# ReboostV2_CAN.net
KiCad netlist of a schematic drawn in Altium Designer
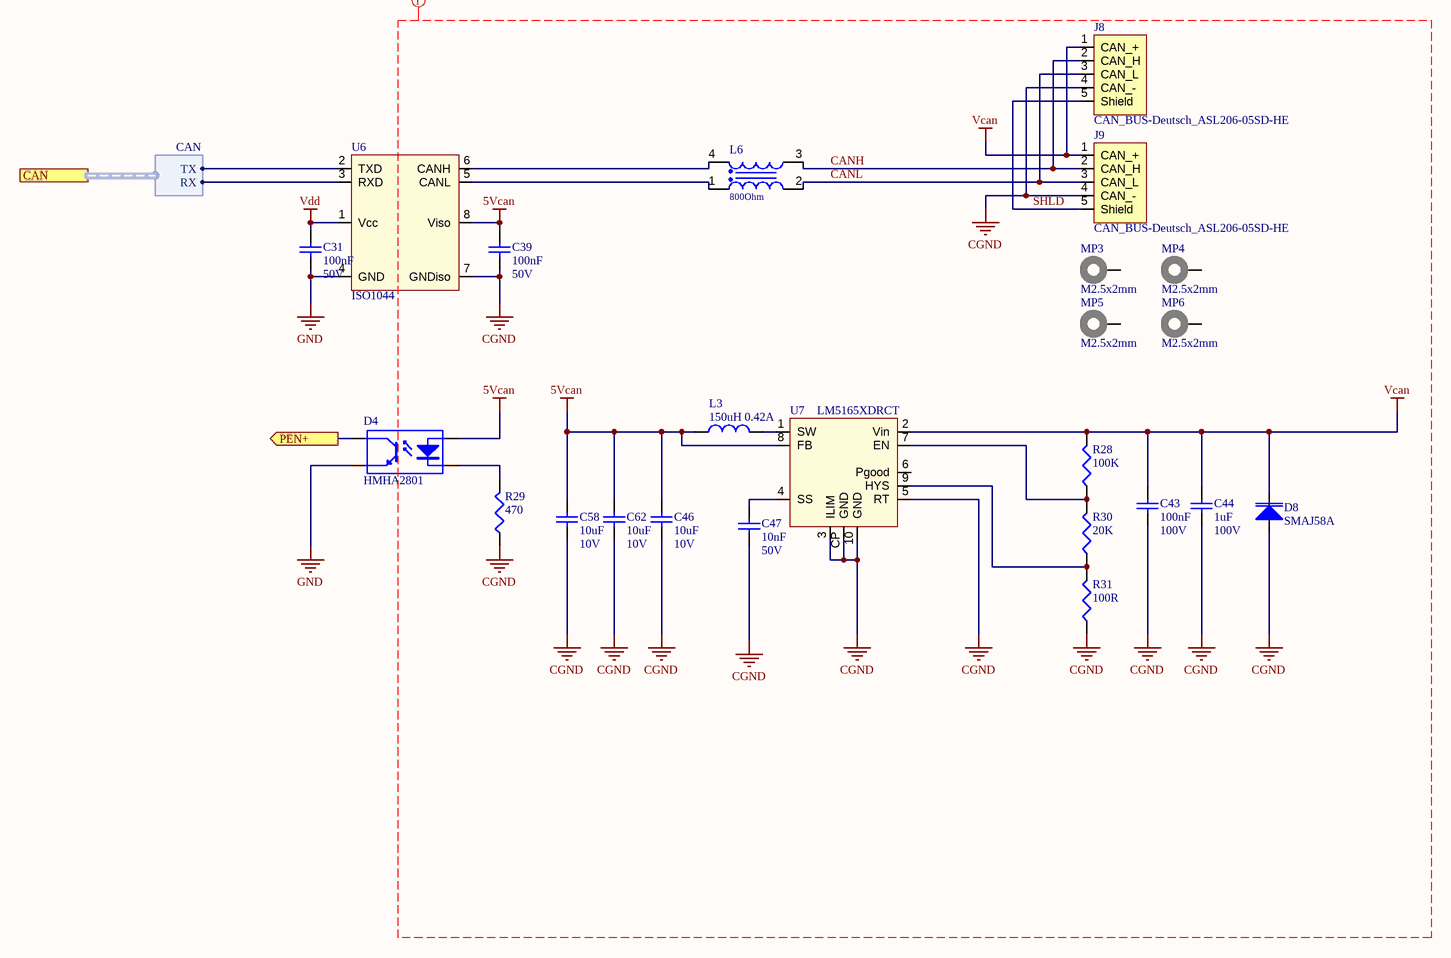
[diagram p0: ReboostV2_CAN.SchDoc]

(export (version "E")
  (design (tool "Eeschema 10.0.6"))
  (components
    (comp (ref "C31")
      (value "100nF")
      (footprint "C0603")
      (description "Capacitor, 100nF, 50V, X7R")
      (fields
        (field (name "VOLTAGE RATING") "50V")
        (field (name "MANUFACTURER") "MULTICOMP")
        (field (name "MANUFACTURER PART NUMBER") "MCCA000255")
      )
      (libsource (lib "Reboostv2") (part "100nF/0603/CER/50V"))
    )
    (comp (ref "C39")
      (value "100nF")
      (footprint "C0603")
      (description "Capacitor, 100nF, 50V, X7R")
      (fields
        (field (name "VOLTAGE RATING") "50V")
        (field (name "MANUFACTURER") "MULTICOMP")
        (field (name "MANUFACTURER PART NUMBER") "MCCA000255")
      )
      (libsource (lib "Reboostv2") (part "100nF/0603/CER/50V"))
    )
    (comp (ref "C43")
      (value "100nF")
      (footprint "C-0805")
      (description "Capacitor, 100nF, 100V, X7R")
      (fields
        (field (name "VOLTAGE RATING") "100V")
        (field (name "MANUFACTURER") "KEMET")
        (field (name "MANUFACTURER PART NUMBER") "C0805C104K1RACTU")
      )
      (libsource (lib "Reboostv2") (part "100nF/0805/CER/100V"))
    )
    (comp (ref "C44")
      (value "1uF")
      (footprint "C-1206")
      (description "Capacitor, 1uF, 100V, X7R")
      (fields
        (field (name "VOLTAGE RATING") "100V")
        (field (name "MANUFACTURER") "AVX")
        (field (name "MANUFACTURER PART NUMBER") "12061C105K4Z2A")
      )
      (libsource (lib "Reboostv2") (part "1uF/1206/CER/100V"))
    )
    (comp (ref "C46")
      (value "10uF")
      (footprint "C-0805")
      (description "Capacitor, 10uF, 10V, X7R")
      (fields
        (field (name "VOLTAGE RATING") "10V")
        (field (name "MANUFACTURER") "MURATA")
        (field (name "MANUFACTURER PART NUMBER") "GRM21BR71A106KE51L")
      )
      (libsource (lib "Reboostv2") (part "10uF/0805/CER/10V"))
    )
    (comp (ref "C47")
      (value "10nF")
      (footprint "C0603")
      (description "Capacitor, 10nF, 50V, X7R")
      (fields
        (field (name "VOLTAGE RATING") "50V")
        (field (name "MANUFACTURER") "KEMET")
        (field (name "MANUFACTURER PART NUMBER") "C0603C103K5RACTU")
      )
      (libsource (lib "Reboostv2") (part "10nF/0603/CER/50V"))
    )
    (comp (ref "C58")
      (value "10uF")
      (footprint "C-0805")
      (description "Capacitor, 10uF, 10V, X7R")
      (fields
        (field (name "VOLTAGE RATING") "10V")
        (field (name "MANUFACTURER") "MURATA")
        (field (name "MANUFACTURER PART NUMBER") "GRM21BR71A106KE51L")
      )
      (libsource (lib "Reboostv2") (part "10uF/0805/CER/10V"))
    )
    (comp (ref "C62")
      (value "10uF")
      (footprint "C-0805")
      (description "Capacitor, 10uF, 10V, X7R")
      (fields
        (field (name "VOLTAGE RATING") "10V")
        (field (name "MANUFACTURER") "MURATA")
        (field (name "MANUFACTURER PART NUMBER") "GRM21BR71A106KE51L")
      )
      (libsource (lib "Reboostv2") (part "10uF/0805/CER/10V"))
    )
    (comp (ref "D4")
      (value "HMHA2801")
      (footprint "FSOP4")
      (description "Optocoupler, Vout:80V, Iin:0.01A")
      (fields (field (name "MANUFACTURER") "FAIRCHILD SEMICONDUCTOR"))
      (libsource (lib "Reboostv2") (part "HMHA2801"))
    )
    (comp (ref "D8")
      (value "SMAJ58A")
      (footprint "SMA")
      (description "Diode TVS, Vrwm: 58V, Vbr: 71.2V, Vc: 93.6V, Ippm: 4.3A")
      (fields (field (name "MANUFACTURER") "MULTICOMP"))
      (libsource (lib "Reboostv2") (part "SMAJ58A"))
    )
    (comp (ref "J8")
      (value "CAN_BUS-Deutsch_ASL206-05SD-HE")
      (footprint "ASL206-05SD-HE")
      (fields
        (field (name "MANUFACTURER") "TE Connectivity")
        (field (name "MANUFACTURER PART NUMBER") "ASL206-05SD-HE")
      )
      (libsource (lib "Reboostv2") (part "CMP-024-0003-1"))
    )
    (comp (ref "J9")
      (value "CAN_BUS-Deutsch_ASL206-05SD-HE")
      (footprint "ASL206-05SD-HE")
      (fields
        (field (name "MANUFACTURER") "TE Connectivity")
        (field (name "MANUFACTURER PART NUMBER") "ASL206-05SD-HE")
      )
      (libsource (lib "Reboostv2") (part "CMP-024-0003-1"))
    )
    (comp (ref "L3")
      (value "150uH 0.42A")
      (footprint "WE-TPC 4828, MH")
      (description "150UH, 30%, 0.42A")
      (fields
        (field (name "MANUFACTURER") "Wurth Elektronik")
        (field (name "MANUFACTURER PART NUMBER") "744043151")
      )
      (libsource (lib "Reboostv2") (part "744043151"))
    )
    (comp (ref "L6")
      (value "800Ohm")
      (footprint "WE-CNSW_1812")
      (description "WE-CNSW SMT Common Mode Line Filter, size 1812, 800Ohm, 1A, 60V")
      (fields
        (field (name "MANUFACTURER PART NUMBER") "744235801")
        (field (name "MANUFACTURER") "Wurth Elektronik")
      )
      (libsource (lib "Reboostv2") (part "744235801"))
    )
    (comp (ref "MP3")
      (value "M2.5x2mm")
      (footprint "9774020151")
      (description "WA-SMSI SMT Steel Spacer, M2.5 Thread Internal, OD 5.1mm, M2.5x2mm")
      (fields
        (field (name "MANUFACTURER PART NUMBER") "9774020151")
        (field (name "MANUFACTURER") "Wurth Elektronik")
      )
      (libsource (lib "Reboostv2") (part "9774020151"))
    )
    (comp (ref "MP4")
      (value "M2.5x2mm")
      (footprint "9774020151")
      (description "WA-SMSI SMT Steel Spacer, M2.5 Thread Internal, OD 5.1mm, M2.5x2mm")
      (fields
        (field (name "MANUFACTURER PART NUMBER") "9774020151")
        (field (name "MANUFACTURER") "Wurth Elektronik")
      )
      (libsource (lib "Reboostv2") (part "9774020151"))
    )
    (comp (ref "MP5")
      (value "M2.5x2mm")
      (footprint "9774020151")
      (description "WA-SMSI SMT Steel Spacer, M2.5 Thread Internal, OD 5.1mm, M2.5x2mm")
      (fields
        (field (name "MANUFACTURER PART NUMBER") "9774020151")
        (field (name "MANUFACTURER") "Wurth Elektronik")
      )
      (libsource (lib "Reboostv2") (part "9774020151"))
    )
    (comp (ref "MP6")
      (value "M2.5x2mm")
      (footprint "9774020151")
      (description "WA-SMSI SMT Steel Spacer, M2.5 Thread Internal, OD 5.1mm, M2.5x2mm")
      (fields
        (field (name "MANUFACTURER PART NUMBER") "9774020151")
        (field (name "MANUFACTURER") "Wurth Elektronik")
      )
      (libsource (lib "Reboostv2") (part "9774020151"))
    )
    (comp (ref "R28")
      (value "100K")
      (footprint "0603")
      (description "Resistor, 100K, 1%, 0.063W, 50V, 100PPM, 0603")
      (fields
        (field (name "MANUFACTURER") "VISHAY DRALORIC")
        (field (name "MANUFACTURER PART NUMBER") "CRCW0603100KFKEA")
      )
      (libsource (lib "Reboostv2") (part "100K/0603/0063W/50V"))
    )
    (comp (ref "R29")
      (value "470")
      (footprint "0603")
      (description "Resistor, 470, 1%, 0.063W, 50V, 100PPM, 0603")
      (fields
        (field (name "MANUFACTURER") "VISHAY DRALORIC")
        (field (name "MANUFACTURER PART NUMBER") "CRCW0603470RFKEA")
      )
      (libsource (lib "Reboostv2") (part "470/0603/0063W/50V"))
    )
    (comp (ref "R30")
      (value "20K")
      (footprint "0603")
      (description "Resistor, 20K, 1%, 0.063W, 50V, 100PPM, 0603")
      (fields
        (field (name "MANUFACTURER") "VISHAY DRALORIC")
        (field (name "MANUFACTURER PART NUMBER") "CRCW060320K0FKEA")
      )
      (libsource (lib "Reboostv2") (part "20K/0603/0063W/50V"))
    )
    (comp (ref "R31")
      (value "100R")
      (footprint "0603")
      (description "Resistor, 100R, 1%, 0.063W, 50V, 200PPM, 0603")
      (fields
        (field (name "MANUFACTURER") "VISHAY DRALORIC")
        (field (name "MANUFACTURER PART NUMBER") "CRCW0603100RFKEA")
      )
      (libsource (lib "Reboostv2") (part "100/0603/0063W/50V"))
    )
    (comp (ref "U6")
      (value "ISO1044")
      (footprint "SO-8")
      (description "ISO1044 Isolated CAN FD Transceiver in Small Package")
      (fields
        (field (name "MANUFACTURER") "Texas Instruments")
        (field (name "MANUFACTURER PART NUMBER") "ISO1044BD")
      )
      (libsource (lib "Reboostv2") (part "ISO1044"))
    )
    (comp (ref "U7")
      (value "LM5165XDRCT")
      (footprint "PWSON10")
      (description "Buck Vreg 150mA 5Vout 5-65Vin")
      (fields (field (name "MANUFACTURER") "Texas Instruments"))
      (libsource (lib "Reboostv2") (part "LM5165X"))
    )
  )
  (nets
    (net (code "2") (name "/CANH") (class "Default")
      (node (ref "J8") (pin "2") (pinfunction "CAN_H_2") (pintype "passive"))
      (node (ref "J9") (pin "2") (pinfunction "CAN_H_2") (pintype "passive"))
      (node (ref "L6") (pin "3") (pinfunction "3_3") (pintype "passive"))
    )
    (net (code "3") (name "/CANL") (class "Default")
      (node (ref "J8") (pin "3") (pinfunction "CAN_L_3") (pintype "passive"))
      (node (ref "J9") (pin "3") (pinfunction "CAN_L_3") (pintype "passive"))
      (node (ref "L6") (pin "2") (pinfunction "2_2") (pintype "passive"))
    )
    (net (code "4") (name "/PEN+") (class "Default")
      (node (ref "D4") (pin "4") (pinfunction "C1_4") (pintype "passive"))
    )
    (net (code "5") (name "/RX") (class "Default")
      (node (ref "U6") (pin "3") (pinfunction "RXD_3") (pintype "passive"))
    )
    (net (code "6") (name "/SHLD") (class "Default")
      (node (ref "J8") (pin "5") (pinfunction "Shield_5") (pintype "passive"))
      (node (ref "J9") (pin "5") (pinfunction "Shield_5") (pintype "passive"))
    )
    (net (code "7") (name "/TX") (class "Default")
      (node (ref "U6") (pin "2") (pinfunction "TXD_2") (pintype "passive"))
    )
    (net (code "9") (name "5Vcan") (class "Default")
      (node (ref "C39") (pin "2") (pinfunction "2_2") (pintype "passive"))
      (node (ref "C46") (pin "2") (pinfunction "2_2") (pintype "passive"))
      (node (ref "C58") (pin "2") (pinfunction "2_2") (pintype "passive"))
      (node (ref "C62") (pin "2") (pinfunction "2_2") (pintype "passive"))
      (node (ref "D4") (pin "1") (pinfunction "A1_1") (pintype "passive"))
      (node (ref "L3") (pin "2") (pinfunction "2_2") (pintype "passive"))
      (node (ref "U6") (pin "8") (pinfunction "Viso_8") (pintype "passive"))
      (node (ref "U7") (pin "8") (pinfunction "FB_8") (pintype "passive"))
    )
    (net (code "10") (name "CGND") (class "Default")
      (node (ref "C39") (pin "1") (pinfunction "1_1") (pintype "passive"))
      (node (ref "C43") (pin "1") (pinfunction "1_1") (pintype "passive"))
      (node (ref "C44") (pin "1") (pinfunction "1_1") (pintype "passive"))
      (node (ref "C46") (pin "1") (pinfunction "1_1") (pintype "passive"))
      (node (ref "C47") (pin "1") (pinfunction "1_1") (pintype "passive"))
      (node (ref "C58") (pin "1") (pinfunction "1_1") (pintype "passive"))
      (node (ref "C62") (pin "1") (pinfunction "1_1") (pintype "passive"))
      (node (ref "D8") (pin "1") (pinfunction "1_1") (pintype "passive"))
      (node (ref "J8") (pin "4") (pinfunction "CAN_-_4") (pintype "passive"))
      (node (ref "J9") (pin "4") (pinfunction "CAN_-_4") (pintype "passive"))
      (node (ref "R29") (pin "1") (pinfunction "1_1") (pintype "passive"))
      (node (ref "R31") (pin "1") (pinfunction "1_1") (pintype "passive"))
      (node (ref "U6") (pin "7") (pinfunction "GNDiso_7") (pintype "passive"))
      (node (ref "U7") (pin "10") (pinfunction "GND_10") (pintype "passive"))
      (node (ref "U7") (pin "3") (pinfunction "ILIM_3") (pintype "passive"))
      (node (ref "U7") (pin "5") (pinfunction "RT_5") (pintype "passive"))
      (node (ref "U7") (pin "CP") (pinfunction "GND_CP") (pintype "passive"))
    )
    (net (code "11") (name "GND") (class "Default")
      (node (ref "C31") (pin "1") (pinfunction "1_1") (pintype "passive"))
      (node (ref "D4") (pin "3") (pinfunction "E1_3") (pintype "passive"))
      (node (ref "U6") (pin "4") (pinfunction "GND_4") (pintype "passive"))
    )
    (net (code "12") (name "Net-(D4-K1)") (class "Default")
      (node (ref "D4") (pin "2") (pinfunction "K1_2") (pintype "passive"))
      (node (ref "R29") (pin "2") (pinfunction "2_2") (pintype "passive"))
    )
    (net (code "13") (name "Net-(U6-CANH)") (class "Default")
      (node (ref "L6") (pin "4") (pinfunction "4_4") (pintype "passive"))
      (node (ref "U6") (pin "6") (pinfunction "CANH_6") (pintype "passive"))
    )
    (net (code "14") (name "Net-(U6-CANL)") (class "Default")
      (node (ref "L6") (pin "1") (pinfunction "1_1") (pintype "passive"))
      (node (ref "U6") (pin "5") (pinfunction "CANL_5") (pintype "passive"))
    )
    (net (code "15") (name "Net-(U7-EN)") (class "Default")
      (node (ref "R28") (pin "1") (pinfunction "1_1") (pintype "passive"))
      (node (ref "R30") (pin "2") (pinfunction "2_2") (pintype "passive"))
      (node (ref "U7") (pin "7") (pinfunction "EN_7") (pintype "passive"))
    )
    (net (code "16") (name "Net-(U7-HYS)") (class "Default")
      (node (ref "R30") (pin "1") (pinfunction "1_1") (pintype "passive"))
      (node (ref "R31") (pin "2") (pinfunction "2_2") (pintype "passive"))
      (node (ref "U7") (pin "9") (pinfunction "HYS_9") (pintype "passive"))
    )
    (net (code "17") (name "Net-(U7-SS)") (class "Default")
      (node (ref "C47") (pin "2") (pinfunction "2_2") (pintype "passive"))
      (node (ref "U7") (pin "4") (pinfunction "SS_4") (pintype "passive"))
    )
    (net (code "18") (name "Net-(U7-SW)") (class "Default")
      (node (ref "L3") (pin "1") (pinfunction "1_1") (pintype "passive"))
      (node (ref "U7") (pin "1") (pinfunction "SW_1") (pintype "passive"))
    )
    (net (code "19") (name "Vcan") (class "Default")
      (node (ref "C43") (pin "2") (pinfunction "2_2") (pintype "passive"))
      (node (ref "C44") (pin "2") (pinfunction "2_2") (pintype "passive"))
      (node (ref "D8") (pin "2") (pinfunction "2_2") (pintype "passive"))
      (node (ref "J8") (pin "1") (pinfunction "CAN_+_1") (pintype "passive"))
      (node (ref "J9") (pin "1") (pinfunction "CAN_+_1") (pintype "passive"))
      (node (ref "R28") (pin "2") (pinfunction "2_2") (pintype "passive"))
      (node (ref "U7") (pin "2") (pinfunction "Vin_2") (pintype "passive"))
    )
    (net (code "20") (name "Vdd") (class "Default")
      (node (ref "C31") (pin "2") (pinfunction "2_2") (pintype "passive"))
      (node (ref "U6") (pin "1") (pinfunction "Vcc_1") (pintype "passive"))
    )
    (net (code "21") (name "unconnected-(MP3-Pad1)") (class "Default")
      (node (ref "MP3") (pin "1") (pinfunction "1_1") (pintype "passive"))
    )
    (net (code "22") (name "unconnected-(MP4-Pad1)") (class "Default")
      (node (ref "MP4") (pin "1") (pinfunction "1_1") (pintype "passive"))
    )
    (net (code "23") (name "unconnected-(MP5-Pad1)") (class "Default")
      (node (ref "MP5") (pin "1") (pinfunction "1_1") (pintype "passive"))
    )
    (net (code "24") (name "unconnected-(MP6-Pad1)") (class "Default")
      (node (ref "MP6") (pin "1") (pinfunction "1_1") (pintype "passive"))
    )
    (net (code "25") (name "unconnected-(U7-Pgood-Pad6)") (class "Default")
      (node (ref "U7") (pin "6") (pinfunction "Pgood_6") (pintype "passive"))
    )
  )
)
